# NavButtons.net
KiCad netlist of a schematic drawn in EAGLE
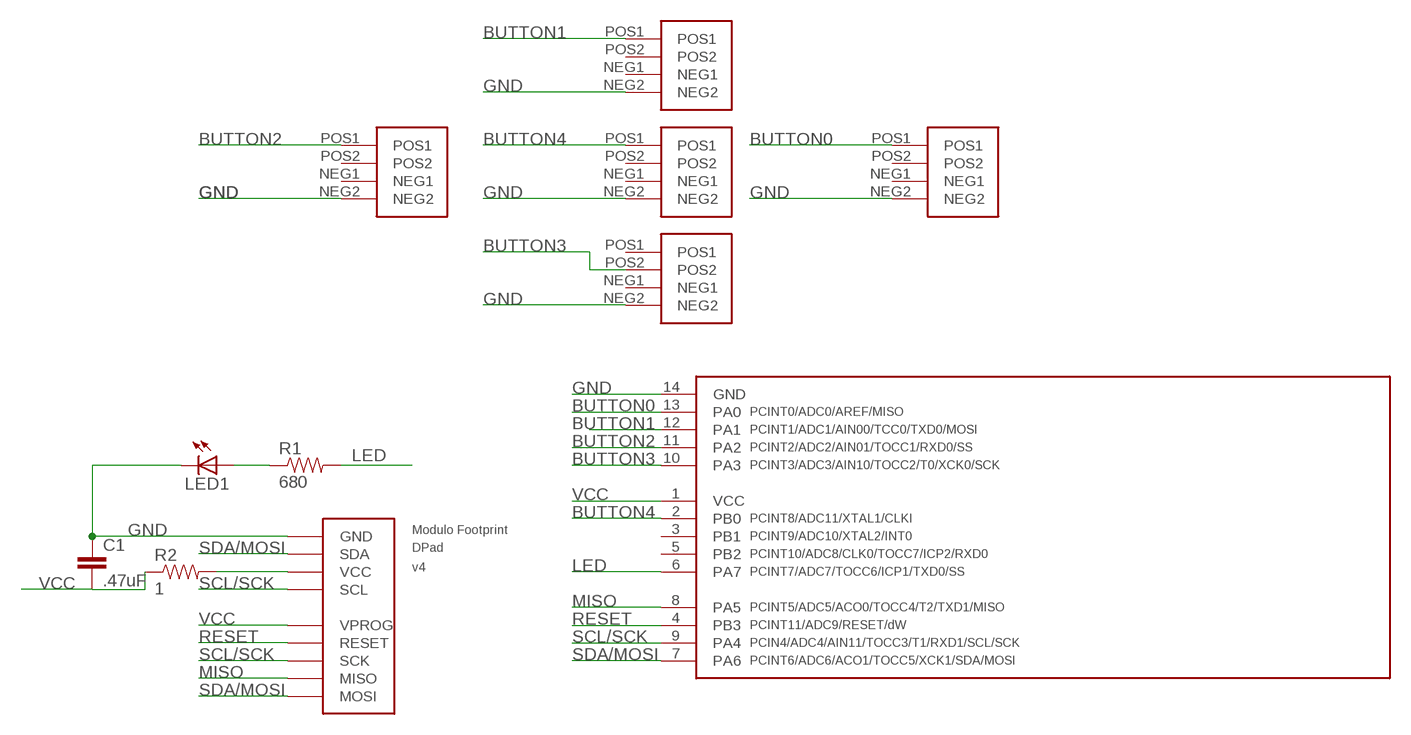
[diagram p0: schematic, sheet 1]

(export (version "E")
  (design (tool "Eeschema 10.0.6"))
  (components
    (comp (ref "B1")
      (value "TACT-SWITCH")
      (footprint "eagle-import:MJTP1138")
      (libsource (lib "eagle-import") (part "TACT-SWITCH"))
    )
    (comp (ref "B3")
      (value "TACT-SWITCH")
      (footprint "eagle-import:MJTP1138")
      (libsource (lib "eagle-import") (part "TACT-SWITCH"))
    )
    (comp (ref "B4")
      (value "TACT-SWITCH")
      (footprint "eagle-import:MJTP1138")
      (libsource (lib "eagle-import") (part "TACT-SWITCH"))
    )
    (comp (ref "B5")
      (value "TACT-SWITCH")
      (footprint "eagle-import:MJTP1138")
      (libsource (lib "eagle-import") (part "TACT-SWITCH"))
    )
    (comp (ref "B7")
      (value "TACT-SWITCH")
      (footprint "eagle-import:MJTP1138")
      (libsource (lib "eagle-import") (part "TACT-SWITCH"))
    )
    (comp (ref "C1")
      (value ".47uF")
      (footprint "eagle-import:0805")
      (libsource (lib "eagle-import") (part "CAP0805"))
    )
    (comp (ref "LED1")
      (value "LEDCHIP-LED0805")
      (footprint "eagle-import:CHIP-LED0805")
      (libsource (lib "eagle-import") (part "LEDCHIP-LED0805"))
    )
    (comp (ref "R1")
      (value "680")
      (footprint "eagle-import:0805")
      (libsource (lib "eagle-import") (part "RESISTOR0805-RES"))
    )
    (comp (ref "R2")
      (value "1")
      (footprint "eagle-import:0805")
      (libsource (lib "eagle-import") (part "SparkFun-Resistors_RESISTOR0805-RES"))
    )
    (comp (ref "U$1")
      (value "TINY841")
      (footprint "eagle-import:SOIC14")
      (libsource (lib "eagle-import") (part "TINY841"))
    )
    (comp (ref "U$2")
      (value "FOOTPRINTFOOTPRINT-2")
      (footprint "eagle-import:FOOTPRINT2")
      (fields (field (name "BOARD") "DPad") (field (name "VERSION") "v4"))
      (libsource (lib "eagle-import") (part "FOOTPRINTFOOTPRINT-2"))
    )
  )
  (nets
    (net (code "1") (name "/BUTTON0") (class "Default")
      (node (ref "B5") (pin "POS1") (pinfunction "POS1_POS1") (pintype "bidirectional"))
      (node (ref "U$1") (pin "13") (pinfunction "PA0_13") (pintype "bidirectional"))
    )
    (net (code "2") (name "/BUTTON1") (class "Default")
      (node (ref "B1") (pin "POS1") (pinfunction "POS1_POS1") (pintype "bidirectional"))
      (node (ref "U$1") (pin "12") (pinfunction "PA1_12") (pintype "bidirectional"))
    )
    (net (code "3") (name "/BUTTON2") (class "Default")
      (node (ref "B3") (pin "POS1") (pinfunction "POS1_POS1") (pintype "bidirectional"))
      (node (ref "U$1") (pin "11") (pinfunction "PA2_11") (pintype "bidirectional"))
    )
    (net (code "4") (name "/BUTTON3") (class "Default")
      (node (ref "B7") (pin "POS2") (pinfunction "POS2_POS2") (pintype "bidirectional"))
      (node (ref "U$1") (pin "10") (pinfunction "PA3_10") (pintype "bidirectional"))
    )
    (net (code "5") (name "/BUTTON4") (class "Default")
      (node (ref "B4") (pin "POS1") (pinfunction "POS1_POS1") (pintype "bidirectional"))
      (node (ref "U$1") (pin "2") (pinfunction "PB0_2") (pintype "bidirectional"))
    )
    (net (code "6") (name "/GND") (class "Default")
      (node (ref "B1") (pin "NEG2") (pinfunction "NEG2_NEG2") (pintype "bidirectional"))
      (node (ref "B3") (pin "NEG2") (pinfunction "NEG2_NEG2") (pintype "bidirectional"))
      (node (ref "B4") (pin "NEG2") (pinfunction "NEG2_NEG2") (pintype "bidirectional"))
      (node (ref "B5") (pin "NEG2") (pinfunction "NEG2_NEG2") (pintype "bidirectional"))
      (node (ref "B7") (pin "NEG2") (pinfunction "NEG2_NEG2") (pintype "bidirectional"))
      (node (ref "C1") (pin "1") (pinfunction "1_1") (pintype "passive"))
      (node (ref "LED1") (pin "C") (pinfunction "C_C") (pintype "passive"))
      (node (ref "U$1") (pin "14") (pinfunction "GND_14") (pintype "bidirectional"))
      (node (ref "U$2") (pin "BUS0") (pinfunction "GND_BUS0") (pintype "bidirectional"))
    )
    (net (code "7") (name "/LED") (class "Default")
      (node (ref "R1") (pin "2") (pinfunction "2_2") (pintype "passive"))
      (node (ref "U$1") (pin "6") (pinfunction "PA7_6") (pintype "bidirectional"))
    )
    (net (code "8") (name "/MISO") (class "Default")
      (node (ref "U$1") (pin "8") (pinfunction "PA5_8") (pintype "bidirectional"))
      (node (ref "U$2") (pin "PROG3") (pinfunction "MISO_PROG3") (pintype "bidirectional"))
    )
    (net (code "9") (name "/RESET") (class "Default")
      (node (ref "U$1") (pin "4") (pinfunction "PB3_4") (pintype "bidirectional"))
      (node (ref "U$2") (pin "PROG1") (pinfunction "RESET_PROG1") (pintype "bidirectional"))
    )
    (net (code "10") (name "/SCL{slash}SCK") (class "Default")
      (node (ref "U$1") (pin "9") (pinfunction "PA4_9") (pintype "bidirectional"))
      (node (ref "U$2") (pin "BUS3") (pinfunction "SCL_BUS3") (pintype "bidirectional"))
      (node (ref "U$2") (pin "PROG2") (pinfunction "SCK_PROG2") (pintype "bidirectional"))
    )
    (net (code "11") (name "/SDA{slash}MOSI") (class "Default")
      (node (ref "U$1") (pin "7") (pinfunction "PA6_7") (pintype "bidirectional"))
      (node (ref "U$2") (pin "BUS1") (pinfunction "SDA_BUS1") (pintype "bidirectional"))
      (node (ref "U$2") (pin "PROG4") (pinfunction "MOSI_PROG4") (pintype "bidirectional"))
    )
    (net (code "12") (name "/VCC") (class "Default")
      (node (ref "C1") (pin "2") (pinfunction "2_2") (pintype "passive"))
      (node (ref "R2") (pin "1") (pinfunction "1_1") (pintype "passive"))
      (node (ref "U$1") (pin "1") (pinfunction "VCC_1") (pintype "bidirectional"))
      (node (ref "U$2") (pin "PROG0") (pinfunction "VPROG_PROG0") (pintype "bidirectional"))
    )
    (net (code "13") (name "Net-(LED1-PadA)") (class "Default")
      (node (ref "LED1") (pin "A") (pinfunction "A_A") (pintype "passive"))
      (node (ref "R1") (pin "1") (pinfunction "1_1") (pintype "passive"))
    )
    (net (code "14") (name "Net-(U$2-VCC)") (class "Default")
      (node (ref "R2") (pin "2") (pinfunction "2_2") (pintype "passive"))
      (node (ref "U$2") (pin "BUS2") (pinfunction "VCC_BUS2") (pintype "bidirectional"))
    )
    (net (code "15") (name "unconnected-(B1-PadNEG1)") (class "Default")
      (node (ref "B1") (pin "NEG1") (pinfunction "NEG1_NEG1") (pintype "bidirectional"))
    )
    (net (code "16") (name "unconnected-(B1-PadPOS2)") (class "Default")
      (node (ref "B1") (pin "POS2") (pinfunction "POS2_POS2") (pintype "bidirectional"))
    )
    (net (code "17") (name "unconnected-(B3-PadNEG1)") (class "Default")
      (node (ref "B3") (pin "NEG1") (pinfunction "NEG1_NEG1") (pintype "bidirectional"))
    )
    (net (code "18") (name "unconnected-(B3-PadPOS2)") (class "Default")
      (node (ref "B3") (pin "POS2") (pinfunction "POS2_POS2") (pintype "bidirectional"))
    )
    (net (code "19") (name "unconnected-(B4-PadNEG1)") (class "Default")
      (node (ref "B4") (pin "NEG1") (pinfunction "NEG1_NEG1") (pintype "bidirectional"))
    )
    (net (code "20") (name "unconnected-(B4-PadPOS2)") (class "Default")
      (node (ref "B4") (pin "POS2") (pinfunction "POS2_POS2") (pintype "bidirectional"))
    )
    (net (code "21") (name "unconnected-(B5-PadNEG1)") (class "Default")
      (node (ref "B5") (pin "NEG1") (pinfunction "NEG1_NEG1") (pintype "bidirectional"))
    )
    (net (code "22") (name "unconnected-(B5-PadPOS2)") (class "Default")
      (node (ref "B5") (pin "POS2") (pinfunction "POS2_POS2") (pintype "bidirectional"))
    )
    (net (code "23") (name "unconnected-(B7-PadNEG1)") (class "Default")
      (node (ref "B7") (pin "NEG1") (pinfunction "NEG1_NEG1") (pintype "bidirectional"))
    )
    (net (code "24") (name "unconnected-(B7-PadPOS1)") (class "Default")
      (node (ref "B7") (pin "POS1") (pinfunction "POS1_POS1") (pintype "bidirectional"))
    )
    (net (code "25") (name "unconnected-(U$1-PB1-Pad3)") (class "Default")
      (node (ref "U$1") (pin "3") (pinfunction "PB1_3") (pintype "bidirectional"))
    )
    (net (code "26") (name "unconnected-(U$1-PB2-Pad5)") (class "Default")
      (node (ref "U$1") (pin "5") (pinfunction "PB2_5") (pintype "bidirectional"))
    )
  )
)
